# card.net
KiCad netlist of a schematic drawn in EAGLE
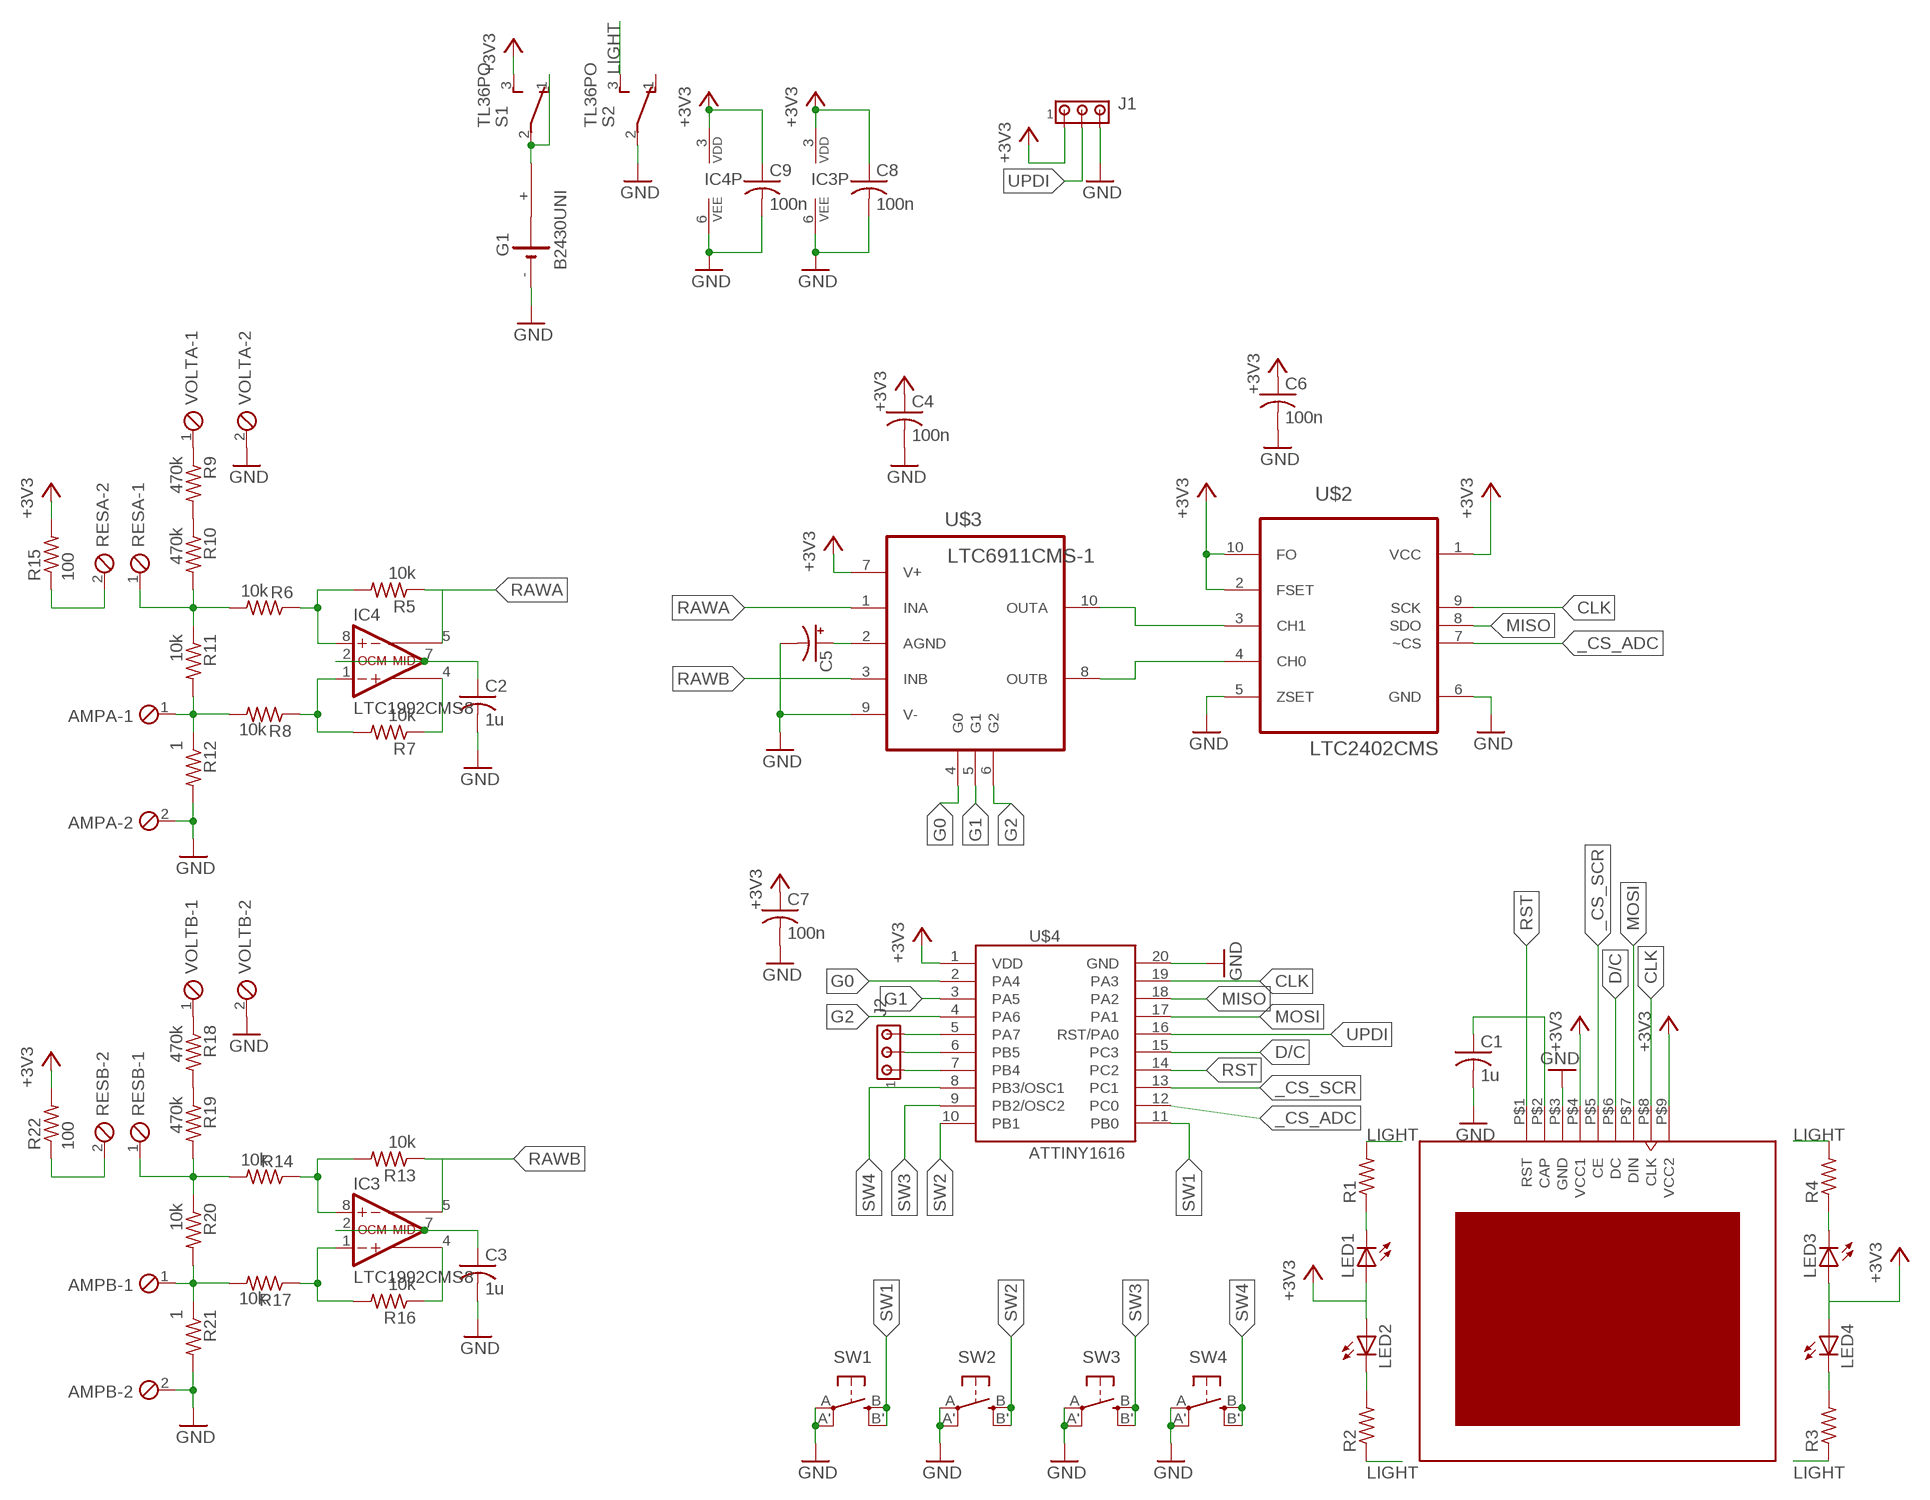
[diagram p0: schematic, sheet 1]

(export (version "E")
  (design (tool "Eeschema 10.0.6"))
  (components
    (comp (ref "AMPA")
      (value "MPT2")
      (footprint "eagle-import:2POL254")
      (libsource (lib "eagle-import") (part "MPT2"))
    )
    (comp (ref "AMPB")
      (value "MPT2")
      (footprint "eagle-import:2POL254")
      (libsource (lib "eagle-import") (part "MPT2"))
    )
    (comp (ref "C1")
      (value "1u")
      (footprint "eagle-import:C0805")
      (libsource (lib "eagle-import") (part "resistor_C-USC0805"))
    )
    (comp (ref "C2")
      (value "1u")
      (footprint "eagle-import:C0805")
      (libsource (lib "eagle-import") (part "resistor_C-USC0805"))
    )
    (comp (ref "C3")
      (value "1u")
      (footprint "eagle-import:C0805")
      (libsource (lib "eagle-import") (part "resistor_C-USC0805"))
    )
    (comp (ref "C4")
      (value "100n")
      (footprint "eagle-import:C0805K")
      (libsource (lib "eagle-import") (part "C-USC0805K"))
    )
    (comp (ref "C5")
      (value "CPOL-USA/3216-18R")
      (footprint "eagle-import:A_3216-18R")
      (libsource (lib "eagle-import") (part "CPOL-USA/3216-18R"))
    )
    (comp (ref "C6")
      (value "100n")
      (footprint "eagle-import:C0805K")
      (libsource (lib "eagle-import") (part "C-USC0805K"))
    )
    (comp (ref "C7")
      (value "100n")
      (footprint "eagle-import:C0805K")
      (libsource (lib "eagle-import") (part "C-USC0805K"))
    )
    (comp (ref "C8")
      (value "100n")
      (footprint "eagle-import:C0805K")
      (libsource (lib "eagle-import") (part "C-USC0805K"))
    )
    (comp (ref "C9")
      (value "100n")
      (footprint "eagle-import:C0805K")
      (libsource (lib "eagle-import") (part "C-USC0805K"))
    )
    (comp (ref "G1")
      (value "B2430UNI")
      (footprint "eagle-import:B2430UNI")
      (libsource (lib "eagle-import") (part "B2430UNI"))
    )
    (comp (ref "IC3")
      (value "LTC1992CMS8")
      (footprint "eagle-import:MSOP8")
      (libsource (lib "eagle-import") (part "LTC1992MS8C"))
    )
    (comp (ref "IC4")
      (value "LTC1992CMS8")
      (footprint "eagle-import:MSOP8")
      (libsource (lib "eagle-import") (part "LTC1992MS8C"))
    )
    (comp (ref "J1")
      (value "MTA03-100")
      (footprint "eagle-import:10X03MTA")
      (libsource (lib "eagle-import") (part "MTA03-100"))
    )
    (comp (ref "J2")
      (value "MTA03-100")
      (footprint "eagle-import:10X03MTA")
      (libsource (lib "eagle-import") (part "MTA03-100"))
    )
    (comp (ref "LED1")
      (value "LEDCHIP-LED0805")
      (footprint "eagle-import:CHIP-LED0805")
      (libsource (lib "eagle-import") (part "LEDCHIP-LED0805"))
    )
    (comp (ref "LED2")
      (value "LEDCHIP-LED0805")
      (footprint "eagle-import:CHIP-LED0805")
      (libsource (lib "eagle-import") (part "LEDCHIP-LED0805"))
    )
    (comp (ref "LED3")
      (value "LEDCHIP-LED0805")
      (footprint "eagle-import:CHIP-LED0805")
      (libsource (lib "eagle-import") (part "LEDCHIP-LED0805"))
    )
    (comp (ref "LED4")
      (value "LEDCHIP-LED0805")
      (footprint "eagle-import:CHIP-LED0805")
      (libsource (lib "eagle-import") (part "LEDCHIP-LED0805"))
    )
    (comp (ref "R1")
      (value "R-US_M0805")
      (footprint "eagle-import:M0805")
      (libsource (lib "eagle-import") (part "R-US_M0805"))
    )
    (comp (ref "R2")
      (value "R-US_M0805")
      (footprint "eagle-import:M0805")
      (libsource (lib "eagle-import") (part "R-US_M0805"))
    )
    (comp (ref "R3")
      (value "R-US_M0805")
      (footprint "eagle-import:M0805")
      (libsource (lib "eagle-import") (part "R-US_M0805"))
    )
    (comp (ref "R4")
      (value "R-US_M0805")
      (footprint "eagle-import:M0805")
      (libsource (lib "eagle-import") (part "R-US_M0805"))
    )
    (comp (ref "R5")
      (value "10k")
      (footprint "eagle-import:M0805")
      (libsource (lib "eagle-import") (part "R-US_M0805"))
    )
    (comp (ref "R6")
      (value "10k")
      (footprint "eagle-import:M0805")
      (libsource (lib "eagle-import") (part "R-US_M0805"))
    )
    (comp (ref "R7")
      (value "10k")
      (footprint "eagle-import:M0805")
      (libsource (lib "eagle-import") (part "R-US_M0805"))
    )
    (comp (ref "R8")
      (value "10k")
      (footprint "eagle-import:M0805")
      (libsource (lib "eagle-import") (part "R-US_M0805"))
    )
    (comp (ref "R9")
      (value "470k")
      (footprint "eagle-import:M0805")
      (libsource (lib "eagle-import") (part "R-US_M0805"))
    )
    (comp (ref "R10")
      (value "470k")
      (footprint "eagle-import:M0805")
      (libsource (lib "eagle-import") (part "R-US_M0805"))
    )
    (comp (ref "R11")
      (value "10k")
      (footprint "eagle-import:M0805")
      (libsource (lib "eagle-import") (part "R-US_M0805"))
    )
    (comp (ref "R12")
      (value "1")
      (footprint "eagle-import:M0805")
      (libsource (lib "eagle-import") (part "R-US_M0805"))
    )
    (comp (ref "R13")
      (value "10k")
      (footprint "eagle-import:M0805")
      (libsource (lib "eagle-import") (part "R-US_M0805"))
    )
    (comp (ref "R14")
      (value "10k")
      (footprint "eagle-import:M0805")
      (libsource (lib "eagle-import") (part "R-US_M0805"))
    )
    (comp (ref "R15")
      (value "100")
      (footprint "eagle-import:M0805")
      (libsource (lib "eagle-import") (part "R-US_M0805"))
    )
    (comp (ref "R16")
      (value "10k")
      (footprint "eagle-import:M0805")
      (libsource (lib "eagle-import") (part "R-US_M0805"))
    )
    (comp (ref "R17")
      (value "10k")
      (footprint "eagle-import:M0805")
      (libsource (lib "eagle-import") (part "R-US_M0805"))
    )
    (comp (ref "R18")
      (value "470k")
      (footprint "eagle-import:M0805")
      (libsource (lib "eagle-import") (part "R-US_M0805"))
    )
    (comp (ref "R19")
      (value "470k")
      (footprint "eagle-import:M0805")
      (libsource (lib "eagle-import") (part "R-US_M0805"))
    )
    (comp (ref "R20")
      (value "10k")
      (footprint "eagle-import:M0805")
      (libsource (lib "eagle-import") (part "R-US_M0805"))
    )
    (comp (ref "R21")
      (value "1")
      (footprint "eagle-import:M0805")
      (libsource (lib "eagle-import") (part "R-US_M0805"))
    )
    (comp (ref "R22")
      (value "100")
      (footprint "eagle-import:M0805")
      (libsource (lib "eagle-import") (part "R-US_M0805"))
    )
    (comp (ref "RESA")
      (value "MPT2")
      (footprint "eagle-import:2POL254")
      (libsource (lib "eagle-import") (part "MPT2"))
    )
    (comp (ref "RESB")
      (value "MPT2")
      (footprint "eagle-import:2POL254")
      (libsource (lib "eagle-import") (part "MPT2"))
    )
    (comp (ref "S1")
      (value "TL36PO")
      (footprint "eagle-import:TL3XPO")
      (libsource (lib "eagle-import") (part "TL36PO"))
    )
    (comp (ref "S2")
      (value "TL36PO")
      (footprint "eagle-import:TL3XPO")
      (libsource (lib "eagle-import") (part "TL36PO"))
    )
    (comp (ref "SW1")
      (value "SPST_TACT-EVQQ2")
      (footprint "eagle-import:EVQ-Q2")
      (libsource (lib "eagle-import") (part "SPST_TACT-EVQQ2"))
    )
    (comp (ref "SW2")
      (value "SPST_TACT-EVQQ2")
      (footprint "eagle-import:EVQ-Q2")
      (libsource (lib "eagle-import") (part "SPST_TACT-EVQQ2"))
    )
    (comp (ref "SW3")
      (value "SPST_TACT-EVQQ2")
      (footprint "eagle-import:EVQ-Q2")
      (libsource (lib "eagle-import") (part "SPST_TACT-EVQQ2"))
    )
    (comp (ref "SW4")
      (value "SPST_TACT-EVQQ2")
      (footprint "eagle-import:EVQ-Q2")
      (libsource (lib "eagle-import") (part "SPST_TACT-EVQQ2"))
    )
    (comp (ref "U$1")
      (value "NOKIA_SCREEN")
      (footprint "eagle-import:NOKIA_SCREEN")
      (libsource (lib "eagle-import") (part "NOKIA_SCREEN"))
    )
    (comp (ref "U$2")
      (value "LTC2402CMS")
      (footprint "eagle-import:MSOP10")
      (libsource (lib "eagle-import") (part "LTC2402CMS"))
    )
    (comp (ref "U$3")
      (value "LTC6911CMS-1")
      (footprint "eagle-import:MSOP10")
      (libsource (lib "eagle-import") (part "LTC6911CMS-1"))
    )
    (comp (ref "U$4")
      (value "ATTINY1616")
      (footprint "eagle-import:SO20W")
      (libsource (lib "eagle-import") (part "ATTINY1616"))
    )
    (comp (ref "VOLTA")
      (value "MPT2")
      (footprint "eagle-import:2POL254")
      (libsource (lib "eagle-import") (part "MPT2"))
    )
    (comp (ref "VOLTB")
      (value "MPT2")
      (footprint "eagle-import:2POL254")
      (libsource (lib "eagle-import") (part "MPT2"))
    )
  )
  (nets
    (net (code "1") (name "+3V3") (class "Default")
      (node (ref "C4") (pin "1") (pinfunction "1_1") (pintype "passive"))
      (node (ref "C6") (pin "1") (pinfunction "1_1") (pintype "passive"))
      (node (ref "C7") (pin "1") (pinfunction "1_1") (pintype "passive"))
      (node (ref "C8") (pin "1") (pinfunction "1_1") (pintype "passive"))
      (node (ref "C9") (pin "1") (pinfunction "1_1") (pintype "passive"))
      (node (ref "IC3") (pin "3") (pinfunction "VDD_3") (pintype "power_in"))
      (node (ref "IC4") (pin "3") (pinfunction "VDD_3") (pintype "power_in"))
      (node (ref "J1") (pin "1") (pinfunction "1_1") (pintype "passive"))
      (node (ref "LED1") (pin "A") (pinfunction "A_A") (pintype "passive"))
      (node (ref "LED2") (pin "A") (pinfunction "A_A") (pintype "passive"))
      (node (ref "LED3") (pin "A") (pinfunction "A_A") (pintype "passive"))
      (node (ref "LED4") (pin "A") (pinfunction "A_A") (pintype "passive"))
      (node (ref "R15") (pin "2") (pinfunction "2_2") (pintype "passive"))
      (node (ref "R22") (pin "2") (pinfunction "2_2") (pintype "passive"))
      (node (ref "S1") (pin "3") (pinfunction "S_3") (pintype "passive"))
      (node (ref "U$1") (pin "P$4") (pinfunction "VCC1_P$4") (pintype "power_in"))
      (node (ref "U$1") (pin "P$9") (pinfunction "VCC2_P$9") (pintype "power_in"))
      (node (ref "U$2") (pin "1") (pinfunction "VCC_1") (pintype "power_in"))
      (node (ref "U$2") (pin "10") (pinfunction "FO_10") (pintype "input"))
      (node (ref "U$2") (pin "2") (pinfunction "FSET_2") (pintype "input"))
      (node (ref "U$3") (pin "7") (pinfunction "V+_7") (pintype "power_in"))
      (node (ref "U$4") (pin "1") (pinfunction "VDD_1") (pintype "power_in"))
    )
    (net (code "2") (name "/LIGHT") (class "Default")
      (node (ref "R1") (pin "2") (pinfunction "2_2") (pintype "passive"))
      (node (ref "R2") (pin "1") (pinfunction "1_1") (pintype "passive"))
      (node (ref "R3") (pin "1") (pinfunction "1_1") (pintype "passive"))
      (node (ref "R4") (pin "2") (pinfunction "2_2") (pintype "passive"))
      (node (ref "S2") (pin "3") (pinfunction "S_3") (pintype "passive"))
    )
    (net (code "3") (name "CLK") (class "Default")
      (node (ref "U$1") (pin "P$8") (pinfunction "CLK_P$8") (pintype "input"))
      (node (ref "U$2") (pin "9") (pinfunction "SCK_9") (pintype "input"))
      (node (ref "U$4") (pin "19") (pinfunction "PA3_19") (pintype "bidirectional"))
    )
    (net (code "4") (name "D{slash}C") (class "Default")
      (node (ref "U$1") (pin "P$6") (pinfunction "DC_P$6") (pintype "input"))
      (node (ref "U$4") (pin "15") (pinfunction "PC3_15") (pintype "bidirectional"))
    )
    (net (code "5") (name "G0") (class "Default")
      (node (ref "U$3") (pin "4") (pinfunction "G0_4") (pintype "input"))
      (node (ref "U$4") (pin "2") (pinfunction "PA4_2") (pintype "bidirectional"))
    )
    (net (code "6") (name "G1") (class "Default")
      (node (ref "U$3") (pin "5") (pinfunction "G1_5") (pintype "input"))
      (node (ref "U$4") (pin "3") (pinfunction "PA5_3") (pintype "bidirectional"))
    )
    (net (code "7") (name "G2") (class "Default")
      (node (ref "U$3") (pin "6") (pinfunction "G2_6") (pintype "input"))
      (node (ref "U$4") (pin "4") (pinfunction "PA6_4") (pintype "bidirectional"))
    )
    (net (code "8") (name "GND") (class "Default")
      (node (ref "AMPA") (pin "2") (pinfunction "1_2") (pintype "passive"))
      (node (ref "AMPB") (pin "2") (pinfunction "1_2") (pintype "passive"))
      (node (ref "C1") (pin "2") (pinfunction "2_2") (pintype "passive"))
      (node (ref "C2") (pin "2") (pinfunction "2_2") (pintype "passive"))
      (node (ref "C3") (pin "2") (pinfunction "2_2") (pintype "passive"))
      (node (ref "C4") (pin "2") (pinfunction "2_2") (pintype "passive"))
      (node (ref "C5") (pin "-") (pinfunction "-_-") (pintype "passive"))
      (node (ref "C6") (pin "2") (pinfunction "2_2") (pintype "passive"))
      (node (ref "C7") (pin "2") (pinfunction "2_2") (pintype "passive"))
      (node (ref "C8") (pin "2") (pinfunction "2_2") (pintype "passive"))
      (node (ref "C9") (pin "2") (pinfunction "2_2") (pintype "passive"))
      (node (ref "G1") (pin "-") (pinfunction "-_-") (pintype "passive"))
      (node (ref "IC3") (pin "6") (pinfunction "VEE_6") (pintype "power_in"))
      (node (ref "IC4") (pin "6") (pinfunction "VEE_6") (pintype "power_in"))
      (node (ref "J1") (pin "3") (pinfunction "3_3") (pintype "passive"))
      (node (ref "R12") (pin "2") (pinfunction "2_2") (pintype "passive"))
      (node (ref "R21") (pin "2") (pinfunction "2_2") (pintype "passive"))
      (node (ref "S2") (pin "2") (pinfunction "P_2") (pintype "passive"))
      (node (ref "SW1") (pin "A") (pinfunction "P_A") (pintype "passive"))
      (node (ref "SW1") (pin "A'") (pinfunction "P1_A'") (pintype "passive"))
      (node (ref "SW2") (pin "A") (pinfunction "P_A") (pintype "passive"))
      (node (ref "SW2") (pin "A'") (pinfunction "P1_A'") (pintype "passive"))
      (node (ref "SW3") (pin "A") (pinfunction "P_A") (pintype "passive"))
      (node (ref "SW3") (pin "A'") (pinfunction "P1_A'") (pintype "passive"))
      (node (ref "SW4") (pin "A") (pinfunction "P_A") (pintype "passive"))
      (node (ref "SW4") (pin "A'") (pinfunction "P1_A'") (pintype "passive"))
      (node (ref "U$1") (pin "P$3") (pinfunction "GND_P$3") (pintype "power_in"))
      (node (ref "U$2") (pin "5") (pinfunction "ZSET_5") (pintype "input"))
      (node (ref "U$2") (pin "6") (pinfunction "GND_6") (pintype "passive"))
      (node (ref "U$3") (pin "9") (pinfunction "V-_9") (pintype "power_in"))
      (node (ref "U$4") (pin "20") (pinfunction "GND_20") (pintype "power_in"))
      (node (ref "VOLTA") (pin "2") (pinfunction "1_2") (pintype "passive"))
      (node (ref "VOLTB") (pin "2") (pinfunction "1_2") (pintype "passive"))
    )
    (net (code "9") (name "MISO") (class "Default")
      (node (ref "U$2") (pin "8") (pinfunction "SDO_8") (pintype "output"))
      (node (ref "U$4") (pin "18") (pinfunction "PA2_18") (pintype "bidirectional"))
    )
    (net (code "10") (name "MOSI") (class "Default")
      (node (ref "U$1") (pin "P$7") (pinfunction "DIN_P$7") (pintype "input"))
      (node (ref "U$4") (pin "17") (pinfunction "PA1_17") (pintype "bidirectional"))
    )
    (net (code "11") (name "Net-(AMPA-Pad1)") (class "Default")
      (node (ref "AMPA") (pin "1") (pinfunction "1_1") (pintype "passive"))
      (node (ref "R11") (pin "2") (pinfunction "2_2") (pintype "passive"))
      (node (ref "R12") (pin "1") (pinfunction "1_1") (pintype "passive"))
      (node (ref "R8") (pin "2") (pinfunction "2_2") (pintype "passive"))
    )
    (net (code "12") (name "Net-(AMPB-Pad1)") (class "Default")
      (node (ref "AMPB") (pin "1") (pinfunction "1_1") (pintype "passive"))
      (node (ref "R17") (pin "2") (pinfunction "2_2") (pintype "passive"))
      (node (ref "R20") (pin "2") (pinfunction "2_2") (pintype "passive"))
      (node (ref "R21") (pin "1") (pinfunction "1_1") (pintype "passive"))
    )
    (net (code "13") (name "Net-(IC3A-+IN)") (class "Default")
      (node (ref "IC3") (pin "8") (pinfunction "+IN_8") (pintype "input"))
      (node (ref "R13") (pin "2") (pinfunction "2_2") (pintype "passive"))
      (node (ref "R14") (pin "1") (pinfunction "1_1") (pintype "passive"))
    )
    (net (code "14") (name "Net-(IC3A-+OUT)") (class "Default")
      (node (ref "IC3") (pin "4") (pinfunction "+OUT_4") (pintype "output"))
      (node (ref "R16") (pin "1") (pinfunction "1_1") (pintype "passive"))
    )
    (net (code "15") (name "Net-(IC3A--IN)") (class "Default")
      (node (ref "IC3") (pin "1") (pinfunction "-IN_1") (pintype "input"))
      (node (ref "R16") (pin "2") (pinfunction "2_2") (pintype "passive"))
      (node (ref "R17") (pin "1") (pinfunction "1_1") (pintype "passive"))
    )
    (net (code "16") (name "Net-(IC3A-MID)") (class "Default")
      (node (ref "C3") (pin "1") (pinfunction "1_1") (pintype "passive"))
      (node (ref "IC3") (pin "2") (pinfunction "OCM_2") (pintype "input"))
      (node (ref "IC3") (pin "7") (pinfunction "MID_7") (pintype "passive"))
    )
    (net (code "17") (name "Net-(IC4A-+IN)") (class "Default")
      (node (ref "IC4") (pin "8") (pinfunction "+IN_8") (pintype "input"))
      (node (ref "R5") (pin "2") (pinfunction "2_2") (pintype "passive"))
      (node (ref "R6") (pin "1") (pinfunction "1_1") (pintype "passive"))
    )
    (net (code "18") (name "Net-(IC4A-+OUT)") (class "Default")
      (node (ref "IC4") (pin "4") (pinfunction "+OUT_4") (pintype "output"))
      (node (ref "R7") (pin "1") (pinfunction "1_1") (pintype "passive"))
    )
    (net (code "19") (name "Net-(IC4A--IN)") (class "Default")
      (node (ref "IC4") (pin "1") (pinfunction "-IN_1") (pintype "input"))
      (node (ref "R7") (pin "2") (pinfunction "2_2") (pintype "passive"))
      (node (ref "R8") (pin "1") (pinfunction "1_1") (pintype "passive"))
    )
    (net (code "20") (name "Net-(IC4A-MID)") (class "Default")
      (node (ref "C2") (pin "1") (pinfunction "1_1") (pintype "passive"))
      (node (ref "IC4") (pin "2") (pinfunction "OCM_2") (pintype "input"))
      (node (ref "IC4") (pin "7") (pinfunction "MID_7") (pintype "passive"))
    )
    (net (code "21") (name "Net-(LED1-PadC)") (class "Default")
      (node (ref "LED1") (pin "C") (pinfunction "C_C") (pintype "passive"))
      (node (ref "R1") (pin "1") (pinfunction "1_1") (pintype "passive"))
    )
    (net (code "22") (name "Net-(LED2-PadC)") (class "Default")
      (node (ref "LED2") (pin "C") (pinfunction "C_C") (pintype "passive"))
      (node (ref "R2") (pin "2") (pinfunction "2_2") (pintype "passive"))
    )
    (net (code "23") (name "Net-(LED3-PadC)") (class "Default")
      (node (ref "LED3") (pin "C") (pinfunction "C_C") (pintype "passive"))
      (node (ref "R4") (pin "1") (pinfunction "1_1") (pintype "passive"))
    )
    (net (code "24") (name "Net-(LED4-PadC)") (class "Default")
      (node (ref "LED4") (pin "C") (pinfunction "C_C") (pintype "passive"))
      (node (ref "R3") (pin "2") (pinfunction "2_2") (pintype "passive"))
    )
    (net (code "25") (name "Net-(R9-Pad1)") (class "Default")
      (node (ref "R9") (pin "1") (pinfunction "1_1") (pintype "passive"))
      (node (ref "VOLTA") (pin "1") (pinfunction "1_1") (pintype "passive"))
    )
    (net (code "26") (name "Net-(R10-Pad1)") (class "Default")
      (node (ref "R10") (pin "1") (pinfunction "1_1") (pintype "passive"))
      (node (ref "R9") (pin "2") (pinfunction "2_2") (pintype "passive"))
    )
    (net (code "27") (name "Net-(R10-Pad2)") (class "Default")
      (node (ref "R10") (pin "2") (pinfunction "2_2") (pintype "passive"))
      (node (ref "R11") (pin "1") (pinfunction "1_1") (pintype "passive"))
      (node (ref "R6") (pin "2") (pinfunction "2_2") (pintype "passive"))
      (node (ref "RESA") (pin "1") (pinfunction "1_1") (pintype "passive"))
    )
    (net (code "28") (name "Net-(R14-Pad2)") (class "Default")
      (node (ref "R14") (pin "2") (pinfunction "2_2") (pintype "passive"))
      (node (ref "R19") (pin "2") (pinfunction "2_2") (pintype "passive"))
      (node (ref "R20") (pin "1") (pinfunction "1_1") (pintype "passive"))
      (node (ref "RESB") (pin "1") (pinfunction "1_1") (pintype "passive"))
    )
    (net (code "29") (name "Net-(R18-Pad1)") (class "Default")
      (node (ref "R18") (pin "1") (pinfunction "1_1") (pintype "passive"))
      (node (ref "VOLTB") (pin "1") (pinfunction "1_1") (pintype "passive"))
    )
    (net (code "30") (name "Net-(R18-Pad2)") (class "Default")
      (node (ref "R18") (pin "2") (pinfunction "2_2") (pintype "passive"))
      (node (ref "R19") (pin "1") (pinfunction "1_1") (pintype "passive"))
    )
    (net (code "31") (name "Net-(RESAB-1)") (class "Default")
      (node (ref "R15") (pin "1") (pinfunction "1_1") (pintype "passive"))
      (node (ref "RESA") (pin "2") (pinfunction "1_2") (pintype "passive"))
    )
    (net (code "32") (name "Net-(RESBB-1)") (class "Default")
      (node (ref "R22") (pin "1") (pinfunction "1_1") (pintype "passive"))
      (node (ref "RESB") (pin "2") (pinfunction "1_2") (pintype "passive"))
    )
    (net (code "33") (name "Net-(S1-O)") (class "Default")
      (node (ref "G1") (pin "+") (pinfunction "+_+") (pintype "passive"))
      (node (ref "S1") (pin "1") (pinfunction "O_1") (pintype "passive"))
      (node (ref "S1") (pin "2") (pinfunction "P_2") (pintype "passive"))
    )
    (net (code "34") (name "Net-(U$1-CAP)") (class "Default")
      (node (ref "C1") (pin "1") (pinfunction "1_1") (pintype "passive"))
      (node (ref "U$1") (pin "P$2") (pinfunction "CAP_P$2") (pintype "passive"))
    )
    (net (code "35") (name "Net-(U$2-CH0)") (class "Default")
      (node (ref "U$2") (pin "4") (pinfunction "CH0_4") (pintype "input"))
      (node (ref "U$3") (pin "8") (pinfunction "OUTB_8") (pintype "output"))
    )
    (net (code "36") (name "Net-(U$2-CH1)") (class "Default")
      (node (ref "U$2") (pin "3") (pinfunction "CH1_3") (pintype "input"))
      (node (ref "U$3") (pin "10") (pinfunction "OUTA_10") (pintype "output"))
    )
    (net (code "37") (name "Net-(U$3-AGND)") (class "Default")
      (node (ref "C5") (pin "+") (pinfunction "+_+") (pintype "passive"))
      (node (ref "U$3") (pin "2") (pinfunction "AGND_2") (pintype "passive"))
    )
    (net (code "38") (name "Net-(U$4-PA7)") (class "Default")
      (node (ref "J2") (pin "3") (pinfunction "3_3") (pintype "passive"))
      (node (ref "U$4") (pin "5") (pinfunction "PA7_5") (pintype "bidirectional"))
    )
    (net (code "39") (name "Net-(U$4-PB4)") (class "Default")
      (node (ref "J2") (pin "1") (pinfunction "1_1") (pintype "passive"))
      (node (ref "U$4") (pin "7") (pinfunction "PB4_7") (pintype "bidirectional"))
    )
    (net (code "40") (name "Net-(U$4-PB5)") (class "Default")
      (node (ref "J2") (pin "2") (pinfunction "2_2") (pintype "passive"))
      (node (ref "U$4") (pin "6") (pinfunction "PB5_6") (pintype "bidirectional"))
    )
    (net (code "41") (name "RAWA") (class "Default")
      (node (ref "IC4") (pin "5") (pinfunction "-OUT_5") (pintype "output"))
      (node (ref "R5") (pin "1") (pinfunction "1_1") (pintype "passive"))
      (node (ref "U$3") (pin "1") (pinfunction "INA_1") (pintype "input"))
    )
    (net (code "42") (name "RAWB") (class "Default")
      (node (ref "IC3") (pin "5") (pinfunction "-OUT_5") (pintype "output"))
      (node (ref "R13") (pin "1") (pinfunction "1_1") (pintype "passive"))
      (node (ref "U$3") (pin "3") (pinfunction "INB_3") (pintype "input"))
    )
    (net (code "43") (name "RST") (class "Default")
      (node (ref "U$1") (pin "P$1") (pinfunction "RST_P$1") (pintype "input"))
      (node (ref "U$4") (pin "14") (pinfunction "PC2_14") (pintype "bidirectional"))
    )
    (net (code "44") (name "SW1") (class "Default")
      (node (ref "SW1") (pin "B") (pinfunction "S_B") (pintype "passive"))
      (node (ref "SW1") (pin "B'") (pinfunction "S1_B'") (pintype "passive"))
      (node (ref "U$4") (pin "11") (pinfunction "PB0_11") (pintype "bidirectional"))
    )
    (net (code "45") (name "SW2") (class "Default")
      (node (ref "SW2") (pin "B") (pinfunction "S_B") (pintype "passive"))
      (node (ref "SW2") (pin "B'") (pinfunction "S1_B'") (pintype "passive"))
      (node (ref "U$4") (pin "10") (pinfunction "PB1_10") (pintype "bidirectional"))
    )
    (net (code "46") (name "SW3") (class "Default")
      (node (ref "SW3") (pin "B") (pinfunction "S_B") (pintype "passive"))
      (node (ref "SW3") (pin "B'") (pinfunction "S1_B'") (pintype "passive"))
      (node (ref "U$4") (pin "9") (pinfunction "PB2/OSC2_9") (pintype "bidirectional"))
    )
    (net (code "47") (name "SW4") (class "Default")
      (node (ref "SW4") (pin "B") (pinfunction "S_B") (pintype "passive"))
      (node (ref "SW4") (pin "B'") (pinfunction "S1_B'") (pintype "passive"))
      (node (ref "U$4") (pin "8") (pinfunction "PB3/OSC1_8") (pintype "bidirectional"))
    )
    (net (code "48") (name "UPDI") (class "Default")
      (node (ref "J1") (pin "2") (pinfunction "2_2") (pintype "passive"))
      (node (ref "U$4") (pin "16") (pinfunction "RST/PA0_16") (pintype "bidirectional"))
    )
    (net (code "49") (name "_CS_ADC") (class "Default")
      (node (ref "U$2") (pin "7") (pinfunction "~{CS}_7") (pintype "input"))
      (node (ref "U$4") (pin "12") (pinfunction "PC0_12") (pintype "bidirectional"))
    )
    (net (code "50") (name "_CS_SCR") (class "Default")
      (node (ref "U$1") (pin "P$5") (pinfunction "CE_P$5") (pintype "input"))
      (node (ref "U$4") (pin "13") (pinfunction "PC1_13") (pintype "bidirectional"))
    )
    (net (code "51") (name "unconnected-(G1-+-Pad+@1)") (class "Default")
      (node (ref "G1") (pin "+@1") (pinfunction "+_+@1") (pintype "passive"))
    )
    (net (code "52") (name "unconnected-(G1-+-Pad+@2)") (class "Default")
      (node (ref "G1") (pin "+@2") (pinfunction "+_+@2") (pintype "passive"))
    )
    (net (code "53") (name "unconnected-(G1-+-Pad+@3)") (class "Default")
      (node (ref "G1") (pin "+@3") (pinfunction "+_+@3") (pintype "passive"))
    )
    (net (code "54") (name "unconnected-(G1-+-Pad+@4)") (class "Default")
      (node (ref "G1") (pin "+@4") (pinfunction "+_+@4") (pintype "passive"))
    )
    (net (code "55") (name "unconnected-(G1---Pad-@1)") (class "Default")
      (node (ref "G1") (pin "-@1") (pinfunction "-_-@1") (pintype "passive"))
    )
    (net (code "56") (name "unconnected-(S2-O-Pad1)") (class "Default")
      (node (ref "S2") (pin "1") (pinfunction "O_1") (pintype "passive"))
    )
  )
)
